# Telescope_Interface_shield.net
KiCad netlist of a schematic drawn in EAGLE
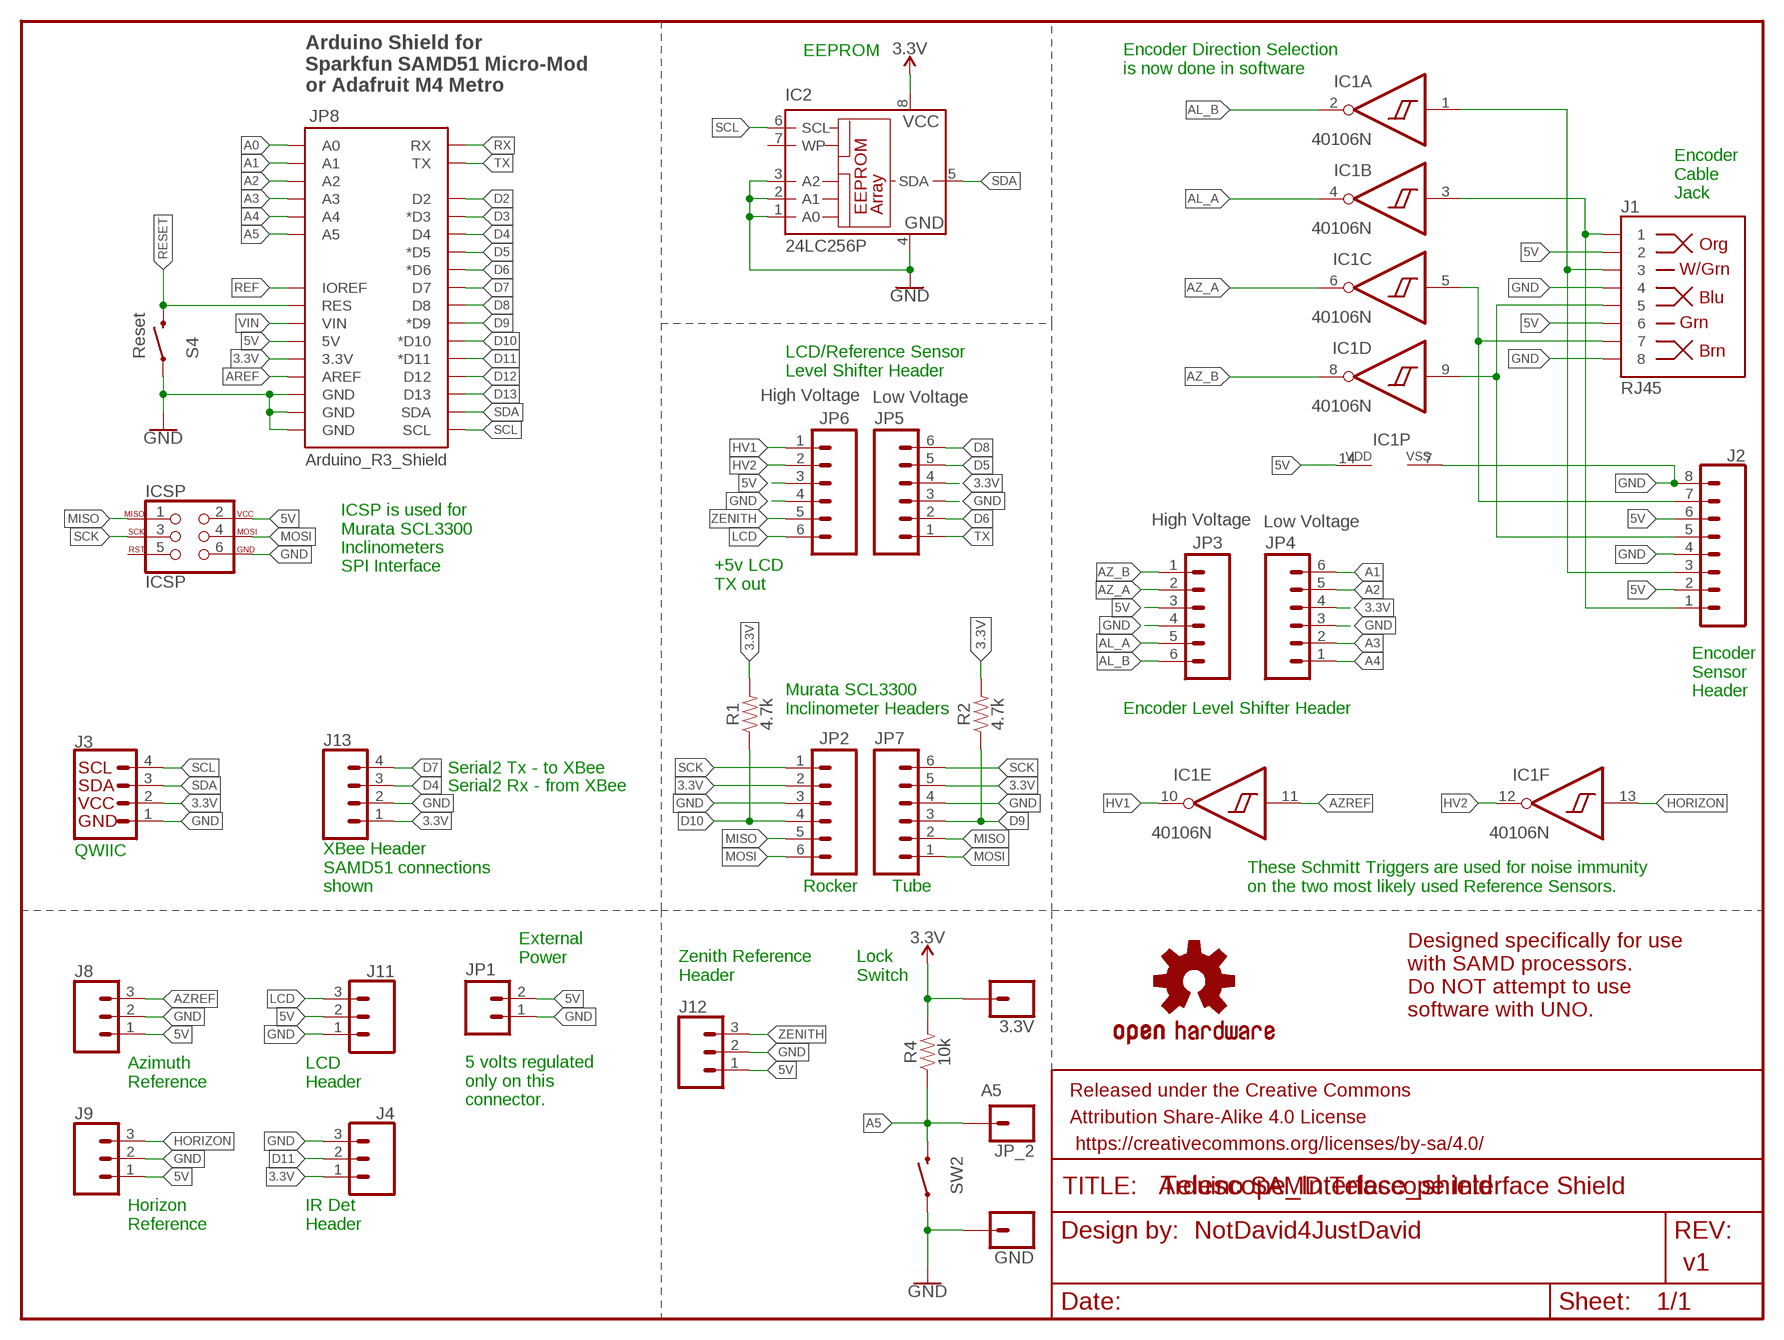
[diagram p0: schematic, sheet 1]

(export (version "E")
  (design (tool "Eeschema 10.0.6"))
  (components
    (comp (ref "3.3V")
      (value "CONN_01")
      (footprint "eagle-import:1X01")
      (libsource (lib "eagle-import") (part "CONN_01"))
    )
    (comp (ref "FRAME1")
      (value "FRAME-LETTER")
      (footprint "eagle-import:CREATIVE_COMMONS")
      (fields (field (name "DESIGNER") "NotDavid4JustDavid") (field (name "REV") "v1"))
      (libsource (lib "eagle-import") (part "FRAME-LETTER"))
    )
    (comp (ref "GND")
      (value "CONN_01")
      (footprint "eagle-import:1X01")
      (libsource (lib "eagle-import") (part "CONN_01"))
    )
    (comp (ref "IC1")
      (value "40106N")
      (footprint "eagle-import:DIL14")
      (libsource (lib "eagle-import") (part "40106N"))
    )
    (comp (ref "IC2")
      (value "24LC256P")
      (footprint "eagle-import:DIL8")
      (fields (field (name "MF") "MICROCHIP") (field (name "MPN") "24LC256-E/P"))
      (libsource (lib "eagle-import") (part "24PLC256"))
    )
    (comp (ref "ICSP")
      (value "ICSP")
      (footprint "eagle-import:2X3")
      (libsource (lib "eagle-import") (part "AVR_SPI_PROG_3X2PTH"))
    )
    (comp (ref "J1")
      (value "RJ45")
      (footprint "eagle-import:RJ45-8")
      (libsource (lib "eagle-import") (part "RJ45-8"))
    )
    (comp (ref "J2")
      (value "CONN_08\"")
      (footprint "eagle-import:1X08")
      (libsource (lib "eagle-import") (part "CONN_08{dblquote}"))
    )
    (comp (ref "J3")
      (value "QWIIC_CONNECTORJS-1MM")
      (footprint "eagle-import:JST04_1MM_RA")
      (libsource (lib "eagle-import") (part "QWIIC_CONNECTORJS-1MM"))
    )
    (comp (ref "J4")
      (value "455-1750-1-ND")
      (footprint "eagle-import:1X03")
      (libsource (lib "eagle-import") (part "CONN_03"))
    )
    (comp (ref "J8")
      (value "455-1750-1-ND")
      (footprint "eagle-import:1X03")
      (libsource (lib "eagle-import") (part "CONN_03"))
    )
    (comp (ref "J9")
      (value "455-1750-1-ND")
      (footprint "eagle-import:1X03")
      (libsource (lib "eagle-import") (part "CONN_03"))
    )
    (comp (ref "J11")
      (value "455-1750-1-ND")
      (footprint "eagle-import:1X03")
      (libsource (lib "eagle-import") (part "CONN_03"))
    )
    (comp (ref "J12")
      (value "455-1750-1-ND")
      (footprint "eagle-import:1X03")
      (libsource (lib "eagle-import") (part "CONN_03"))
    )
    (comp (ref "J13")
      (value "CONN_04PTH")
      (footprint "eagle-import:1X04")
      (libsource (lib "eagle-import") (part "CONN_04PTH"))
    )
    (comp (ref "JP1")
      (value "M02JST-PTH-2")
      (footprint "eagle-import:JST-2-PTH")
      (libsource (lib "eagle-import") (part "M02JST-PTH-2"))
    )
    (comp (ref "JP2")
      (value "M06SIP")
      (footprint "eagle-import:1X06")
      (libsource (lib "eagle-import") (part "M06SIP"))
    )
    (comp (ref "JP3")
      (value "M06SIP")
      (footprint "eagle-import:1X06")
      (libsource (lib "eagle-import") (part "M06SIP"))
    )
    (comp (ref "JP4")
      (value "M06SIP")
      (footprint "eagle-import:1X06")
      (libsource (lib "eagle-import") (part "M06SIP"))
    )
    (comp (ref "JP5")
      (value "M06SIP")
      (footprint "eagle-import:1X06")
      (libsource (lib "eagle-import") (part "M06SIP"))
    )
    (comp (ref "JP6")
      (value "M06SIP")
      (footprint "eagle-import:1X06")
      (libsource (lib "eagle-import") (part "M06SIP"))
    )
    (comp (ref "JP7")
      (value "M06SIP")
      (footprint "eagle-import:1X06")
      (libsource (lib "eagle-import") (part "M06SIP"))
    )
    (comp (ref "JP8")
      (value "ARDUINO_R3_SHIELDR3_PROTO_SHIELD")
      (footprint "eagle-import:UNO_R3_PROTO_SHIELD")
      (libsource (lib "eagle-import") (part "ARDUINO_R3_SHIELDR3_PROTO_SHIELD"))
    )
    (comp (ref "JP_2")
      (value "CONN_01")
      (footprint "eagle-import:1X01")
      (libsource (lib "eagle-import") (part "CONN_01"))
    )
    (comp (ref "LOGO1")
      (value "OSHW-LOGOS")
      (footprint "eagle-import:OSHW-LOGO-S")
      (libsource (lib "eagle-import") (part "OSHW-LOGOS"))
    )
    (comp (ref "R1")
      (value "4.7k")
      (footprint "eagle-import:0603")
      (libsource (lib "eagle-import") (part "4.7KOHM-0603-1/10W-1%"))
    )
    (comp (ref "R2")
      (value "4.7k")
      (footprint "eagle-import:0603")
      (libsource (lib "eagle-import") (part "4.7KOHM-0603-1/10W-1%"))
    )
    (comp (ref "R4")
      (value "10k")
      (footprint "eagle-import:AXIAL-0.3")
      (libsource (lib "eagle-import") (part "10KOHM-HORIZ-1/4W-5%"))
    )
    (comp (ref "S4")
      (value "MOMENTARY-SWITCH-SPST-PTH-6.0MM")
      (footprint "eagle-import:TACTILE_SWITCH_PTH_6.0MM")
      (libsource (lib "eagle-import") (part "MOMENTARY-SWITCH-SPST-PTH-6.0MM"))
    )
    (comp (ref "SW2")
      (value "MOMENTARY-SWITCH-SPST-PTH-6.0MM")
      (footprint "eagle-import:TACTILE_SWITCH_PTH_6.0MM")
      (libsource (lib "eagle-import") (part "MOMENTARY-SWITCH-SPST-PTH-6.0MM"))
    )
  )
  (nets
    (net (code "1") (name "3.3V") (class "Default")
      (node (ref "3.3V") (pin "1") (pinfunction "1_1") (pintype "passive"))
      (node (ref "IC2") (pin "8") (pinfunction "VCC_8") (pintype "power_in"))
      (node (ref "J13") (pin "1") (pinfunction "1_1") (pintype "passive"))
      (node (ref "J3") (pin "2") (pinfunction "2_2") (pintype "power_in"))
      (node (ref "J4") (pin "1") (pinfunction "1_1") (pintype "passive"))
      (node (ref "JP2") (pin "2") (pinfunction "2_2") (pintype "passive"))
      (node (ref "JP4") (pin "4") (pinfunction "4_4") (pintype "passive"))
      (node (ref "JP5") (pin "4") (pinfunction "4_4") (pintype "passive"))
      (node (ref "JP7") (pin "5") (pinfunction "5_5") (pintype "passive"))
      (node (ref "JP8") (pin "3.3V") (pinfunction "3.3V_3.3V") (pintype "bidirectional"))
      (node (ref "R1") (pin "2") (pinfunction "2_2") (pintype "passive"))
      (node (ref "R2") (pin "2") (pinfunction "2_2") (pintype "passive"))
      (node (ref "R4") (pin "P$2") (pinfunction "2_P$2") (pintype "passive"))
    )
    (net (code "2") (name "5V") (class "Default")
      (node (ref "IC1") (pin "14") (pinfunction "VDD_14") (pintype "power_in"))
      (node (ref "ICSP") (pin "2") (pinfunction "2_2") (pintype "passive"))
      (node (ref "J1") (pin "2") (pinfunction "2_2") (pintype "bidirectional"))
      (node (ref "J1") (pin "6") (pinfunction "6_6") (pintype "bidirectional"))
      (node (ref "J11") (pin "2") (pinfunction "2_2") (pintype "passive"))
      (node (ref "J12") (pin "1") (pinfunction "1_1") (pintype "passive"))
      (node (ref "J2") (pin "2") (pinfunction "2_2") (pintype "passive"))
      (node (ref "J2") (pin "6") (pinfunction "6_6") (pintype "passive"))
      (node (ref "J8") (pin "1") (pinfunction "1_1") (pintype "passive"))
      (node (ref "J9") (pin "1") (pinfunction "1_1") (pintype "passive"))
      (node (ref "JP1") (pin "2") (pinfunction "2_2") (pintype "passive"))
      (node (ref "JP3") (pin "3") (pinfunction "3_3") (pintype "passive"))
      (node (ref "JP6") (pin "3") (pinfunction "3_3") (pintype "passive"))
      (node (ref "JP8") (pin "5V") (pinfunction "5V_5V") (pintype "bidirectional"))
    )
    (net (code "3") (name "A0") (class "Default")
      (node (ref "JP8") (pin "A0") (pinfunction "A0_A0") (pintype "bidirectional"))
    )
    (net (code "4") (name "A1") (class "Default")
      (node (ref "JP4") (pin "6") (pinfunction "6_6") (pintype "passive"))
      (node (ref "JP8") (pin "A1") (pinfunction "A1_A1") (pintype "bidirectional"))
    )
    (net (code "5") (name "A2") (class "Default")
      (node (ref "JP4") (pin "5") (pinfunction "5_5") (pintype "passive"))
      (node (ref "JP8") (pin "A2") (pinfunction "A2_A2") (pintype "bidirectional"))
    )
    (net (code "6") (name "A3") (class "Default")
      (node (ref "JP4") (pin "2") (pinfunction "2_2") (pintype "passive"))
      (node (ref "JP8") (pin "A3") (pinfunction "A3_A3") (pintype "bidirectional"))
    )
    (net (code "7") (name "A4") (class "Default")
      (node (ref "JP4") (pin "1") (pinfunction "1_1") (pintype "passive"))
      (node (ref "JP8") (pin "A4") (pinfunction "A4_A4") (pintype "bidirectional"))
    )
    (net (code "8") (name "A5") (class "Default")
      (node (ref "JP8") (pin "A5") (pinfunction "A5_A5") (pintype "bidirectional"))
      (node (ref "JP_2") (pin "1") (pinfunction "1_1") (pintype "passive"))
      (node (ref "R4") (pin "P$1") (pinfunction "1_P$1") (pintype "passive"))
      (node (ref "SW2") (pin "3") (pinfunction "2_3") (pintype "passive"))
    )
    (net (code "9") (name "AL_A") (class "Default")
      (node (ref "IC1") (pin "4") (pinfunction "O_4") (pintype "output"))
      (node (ref "JP3") (pin "5") (pinfunction "5_5") (pintype "passive"))
    )
    (net (code "10") (name "AL_B") (class "Default")
      (node (ref "IC1") (pin "2") (pinfunction "O_2") (pintype "output"))
      (node (ref "JP3") (pin "6") (pinfunction "6_6") (pintype "passive"))
    )
    (net (code "11") (name "AREF") (class "Default")
      (node (ref "JP8") (pin "AREF") (pinfunction "AREF_AREF") (pintype "bidirectional"))
    )
    (net (code "12") (name "AZREF") (class "Default")
      (node (ref "IC1") (pin "11") (pinfunction "I_11") (pintype "input"))
      (node (ref "J8") (pin "3") (pinfunction "3_3") (pintype "passive"))
    )
    (net (code "13") (name "AZ_A") (class "Default")
      (node (ref "IC1") (pin "6") (pinfunction "O_6") (pintype "output"))
      (node (ref "JP3") (pin "2") (pinfunction "2_2") (pintype "passive"))
    )
    (net (code "14") (name "AZ_B") (class "Default")
      (node (ref "IC1") (pin "8") (pinfunction "O_8") (pintype "output"))
      (node (ref "JP3") (pin "1") (pinfunction "1_1") (pintype "passive"))
    )
    (net (code "15") (name "D2") (class "Default")
      (node (ref "JP8") (pin "D2") (pinfunction "D2_D2") (pintype "bidirectional"))
    )
    (net (code "16") (name "D3") (class "Default")
      (node (ref "JP8") (pin "D3") (pinfunction "*D3_D3") (pintype "bidirectional"))
    )
    (net (code "17") (name "D4") (class "Default")
      (node (ref "J13") (pin "3") (pinfunction "3_3") (pintype "passive"))
      (node (ref "JP8") (pin "D4") (pinfunction "D4_D4") (pintype "bidirectional"))
    )
    (net (code "18") (name "D5") (class "Default")
      (node (ref "JP5") (pin "5") (pinfunction "5_5") (pintype "passive"))
      (node (ref "JP8") (pin "D5") (pinfunction "*D5_D5") (pintype "bidirectional"))
    )
    (net (code "19") (name "D6") (class "Default")
      (node (ref "JP5") (pin "2") (pinfunction "2_2") (pintype "passive"))
      (node (ref "JP8") (pin "D6") (pinfunction "*D6_D6") (pintype "bidirectional"))
    )
    (net (code "20") (name "D7") (class "Default")
      (node (ref "J13") (pin "4") (pinfunction "4_4") (pintype "passive"))
      (node (ref "JP8") (pin "D7") (pinfunction "D7_D7") (pintype "bidirectional"))
    )
    (net (code "21") (name "D8") (class "Default")
      (node (ref "JP5") (pin "6") (pinfunction "6_6") (pintype "passive"))
      (node (ref "JP8") (pin "D8") (pinfunction "D8_D8") (pintype "bidirectional"))
    )
    (net (code "22") (name "D9") (class "Default")
      (node (ref "JP7") (pin "3") (pinfunction "3_3") (pintype "passive"))
      (node (ref "JP8") (pin "D9") (pinfunction "*D9_D9") (pintype "bidirectional"))
      (node (ref "R2") (pin "1") (pinfunction "1_1") (pintype "passive"))
    )
    (net (code "23") (name "D10") (class "Default")
      (node (ref "JP2") (pin "4") (pinfunction "4_4") (pintype "passive"))
      (node (ref "JP8") (pin "D10") (pinfunction "*D10_D10") (pintype "bidirectional"))
      (node (ref "R1") (pin "1") (pinfunction "1_1") (pintype "passive"))
    )
    (net (code "24") (name "D11") (class "Default")
      (node (ref "J4") (pin "2") (pinfunction "2_2") (pintype "passive"))
      (node (ref "JP8") (pin "D11") (pinfunction "*D11_D11") (pintype "bidirectional"))
    )
    (net (code "25") (name "D12") (class "Default")
      (node (ref "JP8") (pin "D12") (pinfunction "D12_D12") (pintype "bidirectional"))
    )
    (net (code "26") (name "D13") (class "Default")
      (node (ref "JP8") (pin "D13") (pinfunction "D13_D13") (pintype "bidirectional"))
    )
    (net (code "27") (name "GND") (class "Default")
      (node (ref "GND") (pin "1") (pinfunction "1_1") (pintype "passive"))
      (node (ref "IC1") (pin "7") (pinfunction "VSS_7") (pintype "power_in"))
      (node (ref "IC2") (pin "1") (pinfunction "A0_1") (pintype "input"))
      (node (ref "IC2") (pin "2") (pinfunction "A1_2") (pintype "input"))
      (node (ref "IC2") (pin "3") (pinfunction "A2_3") (pintype "input"))
      (node (ref "IC2") (pin "4") (pinfunction "GND_4") (pintype "power_in"))
      (node (ref "ICSP") (pin "6") (pinfunction "6_6") (pintype "passive"))
      (node (ref "J1") (pin "4") (pinfunction "4_4") (pintype "bidirectional"))
      (node (ref "J1") (pin "8") (pinfunction "8_8") (pintype "bidirectional"))
      (node (ref "J11") (pin "1") (pinfunction "1_1") (pintype "passive"))
      (node (ref "J12") (pin "2") (pinfunction "2_2") (pintype "passive"))
      (node (ref "J13") (pin "2") (pinfunction "2_2") (pintype "passive"))
      (node (ref "J2") (pin "4") (pinfunction "4_4") (pintype "passive"))
      (node (ref "J2") (pin "8") (pinfunction "8_8") (pintype "passive"))
      (node (ref "J3") (pin "1") (pinfunction "1_1") (pintype "power_in"))
      (node (ref "J4") (pin "3") (pinfunction "3_3") (pintype "passive"))
      (node (ref "J8") (pin "2") (pinfunction "2_2") (pintype "passive"))
      (node (ref "J9") (pin "2") (pinfunction "2_2") (pintype "passive"))
      (node (ref "JP1") (pin "1") (pinfunction "1_1") (pintype "passive"))
      (node (ref "JP2") (pin "3") (pinfunction "3_3") (pintype "passive"))
      (node (ref "JP3") (pin "4") (pinfunction "4_4") (pintype "passive"))
      (node (ref "JP4") (pin "3") (pinfunction "3_3") (pintype "passive"))
      (node (ref "JP5") (pin "3") (pinfunction "3_3") (pintype "passive"))
      (node (ref "JP6") (pin "4") (pinfunction "4_4") (pintype "passive"))
      (node (ref "JP7") (pin "4") (pinfunction "4_4") (pintype "passive"))
      (node (ref "JP8") (pin "GND@0") (pinfunction "GND_GND@0") (pintype "bidirectional"))
      (node (ref "JP8") (pin "GND@1") (pinfunction "GND_GND@1") (pintype "bidirectional"))
      (node (ref "JP8") (pin "GND@2") (pinfunction "GND_GND@2") (pintype "bidirectional"))
      (node (ref "S4") (pin "1") (pinfunction "1_1") (pintype "passive"))
      (node (ref "SW2") (pin "1") (pinfunction "1_1") (pintype "passive"))
    )
    (net (code "28") (name "HORIZON") (class "Default")
      (node (ref "IC1") (pin "13") (pinfunction "I_13") (pintype "input"))
      (node (ref "J9") (pin "3") (pinfunction "3_3") (pintype "passive"))
    )
    (net (code "29") (name "HV1") (class "Default")
      (node (ref "IC1") (pin "10") (pinfunction "O_10") (pintype "output"))
      (node (ref "JP6") (pin "1") (pinfunction "1_1") (pintype "passive"))
    )
    (net (code "30") (name "HV2") (class "Default")
      (node (ref "IC1") (pin "12") (pinfunction "O_12") (pintype "output"))
      (node (ref "JP6") (pin "2") (pinfunction "2_2") (pintype "passive"))
    )
    (net (code "31") (name "LCD") (class "Default")
      (node (ref "J11") (pin "3") (pinfunction "3_3") (pintype "passive"))
      (node (ref "JP6") (pin "6") (pinfunction "6_6") (pintype "passive"))
    )
    (net (code "32") (name "MISO") (class "Default")
      (node (ref "ICSP") (pin "1") (pinfunction "1_1") (pintype "passive"))
      (node (ref "JP2") (pin "5") (pinfunction "5_5") (pintype "passive"))
      (node (ref "JP7") (pin "2") (pinfunction "2_2") (pintype "passive"))
    )
    (net (code "33") (name "MOSI") (class "Default")
      (node (ref "ICSP") (pin "4") (pinfunction "4_4") (pintype "passive"))
      (node (ref "JP2") (pin "6") (pinfunction "6_6") (pintype "passive"))
      (node (ref "JP7") (pin "1") (pinfunction "1_1") (pintype "passive"))
    )
    (net (code "34") (name "Net-(IC1A-I)") (class "Default")
      (node (ref "IC1") (pin "1") (pinfunction "I_1") (pintype "input"))
      (node (ref "J1") (pin "3") (pinfunction "3_3") (pintype "bidirectional"))
      (node (ref "J2") (pin "3") (pinfunction "3_3") (pintype "passive"))
    )
    (net (code "35") (name "Net-(IC1B-I)") (class "Default")
      (node (ref "IC1") (pin "3") (pinfunction "I_3") (pintype "input"))
      (node (ref "J1") (pin "1") (pinfunction "1_1") (pintype "bidirectional"))
      (node (ref "J2") (pin "1") (pinfunction "1_1") (pintype "passive"))
    )
    (net (code "36") (name "Net-(IC1C-I)") (class "Default")
      (node (ref "IC1") (pin "5") (pinfunction "I_5") (pintype "input"))
      (node (ref "J1") (pin "7") (pinfunction "7_7") (pintype "bidirectional"))
      (node (ref "J2") (pin "7") (pinfunction "7_7") (pintype "passive"))
    )
    (net (code "37") (name "Net-(IC1D-I)") (class "Default")
      (node (ref "IC1") (pin "9") (pinfunction "I_9") (pintype "input"))
      (node (ref "J1") (pin "5") (pinfunction "5_5") (pintype "bidirectional"))
      (node (ref "J2") (pin "5") (pinfunction "5_5") (pintype "passive"))
    )
    (net (code "38") (name "REF") (class "Default")
      (node (ref "JP8") (pin "IOREF") (pinfunction "IOREF_IOREF") (pintype "bidirectional"))
    )
    (net (code "39") (name "RESET") (class "Default")
      (node (ref "JP8") (pin "RES") (pinfunction "RES_RES") (pintype "bidirectional"))
      (node (ref "S4") (pin "3") (pinfunction "2_3") (pintype "passive"))
    )
    (net (code "40") (name "RX") (class "Default")
      (node (ref "JP8") (pin "RX") (pinfunction "RX_RX") (pintype "bidirectional"))
    )
    (net (code "41") (name "SCK") (class "Default")
      (node (ref "ICSP") (pin "3") (pinfunction "3_3") (pintype "passive"))
      (node (ref "JP2") (pin "1") (pinfunction "1_1") (pintype "passive"))
      (node (ref "JP7") (pin "6") (pinfunction "6_6") (pintype "passive"))
    )
    (net (code "42") (name "SCL") (class "Default")
      (node (ref "IC2") (pin "6") (pinfunction "SCL_6") (pintype "input"))
      (node (ref "J3") (pin "4") (pinfunction "4_4") (pintype "passive"))
      (node (ref "JP8") (pin "SCL") (pinfunction "SCL_SCL") (pintype "bidirectional"))
    )
    (net (code "43") (name "SDA") (class "Default")
      (node (ref "IC2") (pin "5") (pinfunction "SDA_5") (pintype "bidirectional"))
      (node (ref "J3") (pin "3") (pinfunction "3_3") (pintype "passive"))
      (node (ref "JP8") (pin "SDA") (pinfunction "SDA_SDA") (pintype "bidirectional"))
    )
    (net (code "44") (name "TX") (class "Default")
      (node (ref "JP5") (pin "1") (pinfunction "1_1") (pintype "passive"))
      (node (ref "JP8") (pin "TX") (pinfunction "TX_TX") (pintype "bidirectional"))
    )
    (net (code "45") (name "VIN") (class "Default")
      (node (ref "JP8") (pin "VIN") (pinfunction "VIN_VIN") (pintype "bidirectional"))
    )
    (net (code "46") (name "ZENITH") (class "Default")
      (node (ref "J12") (pin "3") (pinfunction "3_3") (pintype "passive"))
      (node (ref "JP6") (pin "5") (pinfunction "5_5") (pintype "passive"))
    )
    (net (code "47") (name "unconnected-(IC2-WP-Pad7)") (class "Default")
      (node (ref "IC2") (pin "7") (pinfunction "WP_7") (pintype "input"))
    )
    (net (code "48") (name "unconnected-(ICSP-Pad5)") (class "Default")
      (node (ref "ICSP") (pin "5") (pinfunction "5_5") (pintype "passive"))
    )
  )
)
